# PMU.net
KiCad netlist of a schematic drawn in Altium Designer
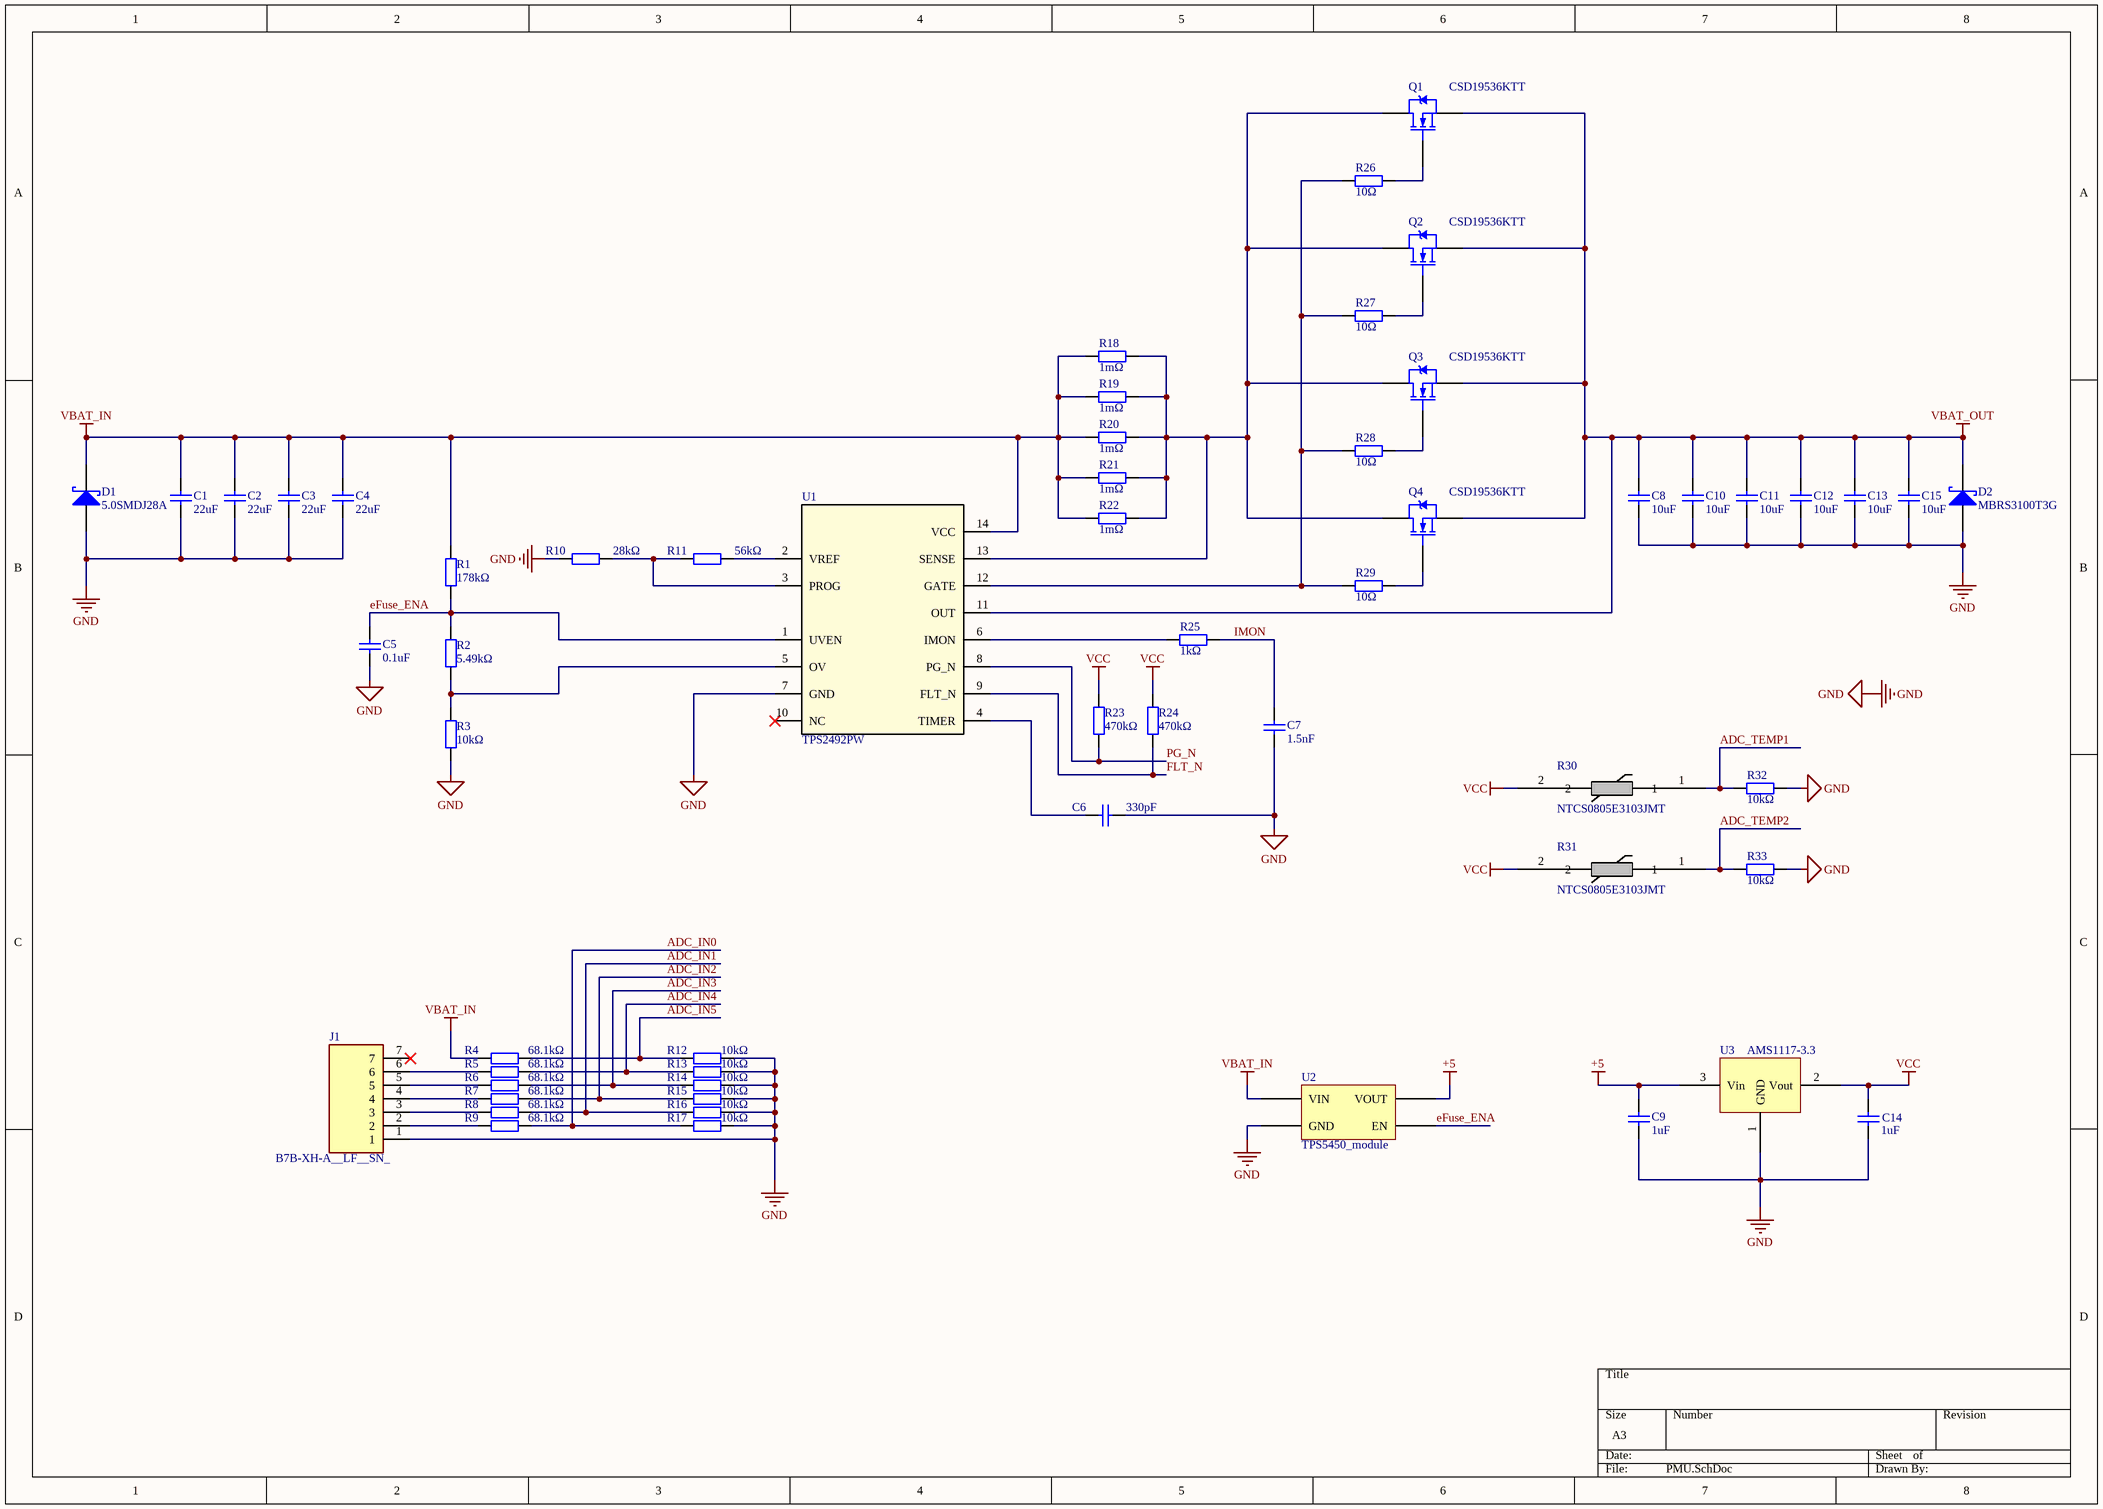
[diagram p0: PMU.SchDoc]

(export (version "E")
  (design (tool "Eeschema 10.0.6"))
  (components
    (comp (ref "C1")
      (value "22uF")
      (footprint "C1210")
      (description "VJ1210Y104MXCAT")
      (libsource (lib "NetTie") (part "Capacitor"))
    )
    (comp (ref "C2")
      (value "22uF")
      (footprint "C1210")
      (description "VJ1210Y104MXCAT")
      (libsource (lib "NetTie") (part "Capacitor"))
    )
    (comp (ref "C3")
      (value "22uF")
      (footprint "C1210")
      (description "VJ1210Y104MXCAT")
      (libsource (lib "NetTie") (part "Capacitor"))
    )
    (comp (ref "C4")
      (value "22uF")
      (footprint "C1210")
      (description "VJ1210Y104MXCAT")
      (libsource (lib "NetTie") (part "Capacitor"))
    )
    (comp (ref "C5") (value "0.1uF") (footprint "C0603") (libsource (lib "NetTie") (part "Capacitor")))
    (comp (ref "C6") (value "330pF") (footprint "C0603") (libsource (lib "NetTie") (part "Capacitor")))
    (comp (ref "C7") (value "1.5nF") (footprint "C0603") (libsource (lib "NetTie") (part "Capacitor")))
    (comp (ref "C8")
      (value "10uF")
      (footprint "C1210")
      (description "VJ1210Y104MXCAT")
      (libsource (lib "NetTie") (part "Capacitor"))
    )
    (comp (ref "C9")
      (value "1uF")
      (footprint "C0603")
      (description "VJ1210Y104MXCAT")
      (libsource (lib "NetTie") (part "Capacitor"))
    )
    (comp (ref "C10")
      (value "10uF")
      (footprint "C1210")
      (description "VJ1210Y104MXCAT")
      (libsource (lib "NetTie") (part "Capacitor"))
    )
    (comp (ref "C11")
      (value "10uF")
      (footprint "C1210")
      (description "VJ1210Y104MXCAT")
      (libsource (lib "NetTie") (part "Capacitor"))
    )
    (comp (ref "C12")
      (value "10uF")
      (footprint "C1210")
      (description "VJ1210Y104MXCAT")
      (libsource (lib "NetTie") (part "Capacitor"))
    )
    (comp (ref "C13")
      (value "10uF")
      (footprint "C1210")
      (description "VJ1210Y104MXCAT")
      (libsource (lib "NetTie") (part "Capacitor"))
    )
    (comp (ref "C14")
      (value "1uF")
      (footprint "C0603")
      (description "VJ1210Y104MXCAT")
      (libsource (lib "NetTie") (part "Capacitor"))
    )
    (comp (ref "C15")
      (value "10uF")
      (footprint "C1210")
      (description "VJ1210Y104MXCAT")
      (libsource (lib "NetTie") (part "Capacitor"))
    )
    (comp (ref "D1")
      (value "5.0SMDJ28A")
      (footprint "SMA(DO-214AC)")
      (libsource (lib "CommonUsedComponents") (part "Diode_Schottky"))
    )
    (comp (ref "D2")
      (value "MBRS3100T3G")
      (footprint "SMA(DO-214AC)")
      (description "Schottky Diodes & Rectifiers 3A 100V")
      (libsource (lib "CommonUsedComponents") (part "Diode_Schottky"))
    )
    (comp (ref "J1")
      (value "B7B-XH-A__LF__SN_")
      (footprint "SamacSys:SHDR7W64P0X250_1X7_1990X575X700P")
      (description "Connector")
      (fields (field (name "MANUFACTURER_PART_NUMBER") "B7B-XH-A (LF)(SN)"))
      (libsource (lib "Connectors") (part "B7B-XH-A__LF__SN_"))
    )
    (comp (ref "Q1")
      (value "CSD19536KTT")
      (footprint "KTT0002A")
      (description "100-V N-Channel NexFET™ Power MOSFET")
      (libsource (lib "NetTie") (part "NMOSFET"))
    )
    (comp (ref "Q2")
      (value "CSD19536KTT")
      (footprint "KTT0002A")
      (description "100-V N-Channel NexFET™ Power MOSFET")
      (libsource (lib "NetTie") (part "NMOSFET"))
    )
    (comp (ref "Q3")
      (value "CSD19536KTT")
      (footprint "KTT0002A")
      (description "100-V N-Channel NexFET™ Power MOSFET")
      (libsource (lib "NetTie") (part "NMOSFET"))
    )
    (comp (ref "Q4")
      (value "CSD19536KTT")
      (footprint "KTT0002A")
      (description "100-V N-Channel NexFET™ Power MOSFET")
      (libsource (lib "NetTie") (part "NMOSFET"))
    )
    (comp (ref "R1") (value "178kΩ") (footprint "R0603") (libsource (lib "NetTie") (part "Resistor")))
    (comp (ref "R2") (value "5.49kΩ") (footprint "R0603") (libsource (lib "NetTie") (part "Resistor")))
    (comp (ref "R3") (value "10kΩ") (footprint "R0603") (libsource (lib "NetTie") (part "Resistor")))
    (comp (ref "R4") (value "68.1kΩ") (footprint "R0603") (libsource (lib "") (part "Resistor_2")))
    (comp (ref "R5") (value "68.1kΩ") (footprint "R0603") (libsource (lib "") (part "Resistor_2")))
    (comp (ref "R6") (value "68.1kΩ") (footprint "R0603") (libsource (lib "") (part "Resistor_2")))
    (comp (ref "R7") (value "68.1kΩ") (footprint "R0603") (libsource (lib "") (part "Resistor_2")))
    (comp (ref "R8") (value "68.1kΩ") (footprint "R0603") (libsource (lib "") (part "Resistor_2")))
    (comp (ref "R9") (value "68.1kΩ") (footprint "R0603") (libsource (lib "") (part "Resistor_2")))
    (comp (ref "R10") (value "28kΩ") (footprint "R0603") (libsource (lib "") (part "Resistor_1")))
    (comp (ref "R11") (value "56kΩ") (footprint "R0603") (libsource (lib "") (part "Resistor_1")))
    (comp (ref "R12") (value "10kΩ") (footprint "R0603") (libsource (lib "") (part "Resistor_2")))
    (comp (ref "R13") (value "10kΩ") (footprint "R0603") (libsource (lib "") (part "Resistor_2")))
    (comp (ref "R14") (value "10kΩ") (footprint "R0603") (libsource (lib "") (part "Resistor_2")))
    (comp (ref "R15") (value "10kΩ") (footprint "R0603") (libsource (lib "") (part "Resistor_2")))
    (comp (ref "R16") (value "10kΩ") (footprint "R0603") (libsource (lib "") (part "Resistor_2")))
    (comp (ref "R17") (value "10kΩ") (footprint "R0603") (libsource (lib "") (part "Resistor_2")))
    (comp (ref "R18")
      (value "1mΩ")
      (footprint "2512_R")
      (description "CHSA2512R0010F")
      (libsource (lib "") (part "Resistor_1"))
    )
    (comp (ref "R19")
      (value "1mΩ")
      (footprint "2512_R")
      (description "CHSA2512R0010F")
      (libsource (lib "") (part "Resistor_1"))
    )
    (comp (ref "R20")
      (value "1mΩ")
      (footprint "2512_R")
      (description "CHSA2512R0010F")
      (libsource (lib "") (part "Resistor_1"))
    )
    (comp (ref "R21")
      (value "1mΩ")
      (footprint "2512_R")
      (description "CHSA2512R0010F")
      (libsource (lib "") (part "Resistor_1"))
    )
    (comp (ref "R22")
      (value "1mΩ")
      (footprint "2512_R")
      (description "CHSA2512R0010F")
      (libsource (lib "") (part "Resistor_1"))
    )
    (comp (ref "R23") (value "470kΩ") (footprint "R0603") (libsource (lib "") (part "Resistor_3")))
    (comp (ref "R24") (value "470kΩ") (footprint "R0603") (libsource (lib "") (part "Resistor_3")))
    (comp (ref "R25") (value "1kΩ") (footprint "R0603") (libsource (lib "") (part "Resistor_2")))
    (comp (ref "R26") (value "10Ω") (footprint "R0603") (libsource (lib "") (part "Resistor_2")))
    (comp (ref "R27") (value "10Ω") (footprint "R0603") (libsource (lib "") (part "Resistor_2")))
    (comp (ref "R28") (value "10Ω") (footprint "R0603") (libsource (lib "") (part "Resistor_2")))
    (comp (ref "R29") (value "10Ω") (footprint "R0603") (libsource (lib "") (part "Resistor_2")))
    (comp (ref "R30")
      (value "NTCS0805E3103JMT")
      (footprint "NTCS0805_VIS")
      (description "THERMISTOR NTC 10KOHM 3570K 0805")
      (fields (field (name "TOLERANCE") "5%"))
      (libsource (lib "Altium Content Vault") (part "NTCS0805E3103JMT"))
    )
    (comp (ref "R31")
      (value "NTCS0805E3103JMT")
      (footprint "NTCS0805_VIS")
      (description "THERMISTOR NTC 10KOHM 3570K 0805")
      (fields (field (name "TOLERANCE") "5%"))
      (libsource (lib "Altium Content Vault") (part "NTCS0805E3103JMT"))
    )
    (comp (ref "R32") (value "10kΩ") (footprint "R0603") (libsource (lib "") (part "Resistor_1")))
    (comp (ref "R33") (value "10kΩ") (footprint "R0603") (libsource (lib "") (part "Resistor_1")))
    (comp (ref "U1")
      (value "TPS2492PW")
      (footprint "PW0014A_N")
      (libsource (lib "PowerICs") (part "TPS2492PW"))
    )
    (comp (ref "U2")
      (value "TPS5450_module")
      (footprint "TPS5450_module")
      (libsource (lib "PowerICs") (part "TPS5450_module"))
    )
    (comp (ref "U3")
      (value "AMS1117-3.3")
      (footprint "SOT-223")
      (description "C347222")
      (libsource (lib "PowerICs") (part "AMS1117-3.3"))
    )
  )
  (nets
    (net (code "1") (name "+5") (class "Default")
      (node (ref "C9") (pin "2") (pinfunction "2_2") (pintype "passive"))
      (node (ref "U2") (pin "4") (pinfunction "VOUT_4") (pintype "passive"))
      (node (ref "U3") (pin "3") (pinfunction "Vin_3") (pintype "passive"))
    )
    (net (code "2") (name "/ADC_IN0") (class "Default")
      (node (ref "R17") (pin "2") (pinfunction "2_2") (pintype "passive"))
      (node (ref "R9") (pin "1") (pinfunction "1_1") (pintype "passive"))
    )
    (net (code "3") (name "/ADC_IN1") (class "Default")
      (node (ref "R16") (pin "2") (pinfunction "2_2") (pintype "passive"))
      (node (ref "R8") (pin "1") (pinfunction "1_1") (pintype "passive"))
    )
    (net (code "4") (name "/ADC_IN2") (class "Default")
      (node (ref "R15") (pin "2") (pinfunction "2_2") (pintype "passive"))
      (node (ref "R7") (pin "1") (pinfunction "1_1") (pintype "passive"))
    )
    (net (code "5") (name "/ADC_IN3") (class "Default")
      (node (ref "R14") (pin "2") (pinfunction "2_2") (pintype "passive"))
      (node (ref "R6") (pin "1") (pinfunction "1_1") (pintype "passive"))
    )
    (net (code "6") (name "/ADC_IN4") (class "Default")
      (node (ref "R13") (pin "2") (pinfunction "2_2") (pintype "passive"))
      (node (ref "R5") (pin "1") (pinfunction "1_1") (pintype "passive"))
    )
    (net (code "7") (name "/ADC_IN5") (class "Default")
      (node (ref "R12") (pin "2") (pinfunction "2_2") (pintype "passive"))
      (node (ref "R4") (pin "1") (pinfunction "1_1") (pintype "passive"))
    )
    (net (code "8") (name "/ADC_TEMP1") (class "Default")
      (node (ref "R30") (pin "1") (pinfunction "1_1") (pintype "passive"))
      (node (ref "R32") (pin "1") (pinfunction "1_1") (pintype "passive"))
    )
    (net (code "9") (name "/ADC_TEMP2") (class "Default")
      (node (ref "R31") (pin "1") (pinfunction "1_1") (pintype "passive"))
      (node (ref "R33") (pin "1") (pinfunction "1_1") (pintype "passive"))
    )
    (net (code "10") (name "/FLT_N") (class "Default")
      (node (ref "R24") (pin "2") (pinfunction "2_2") (pintype "passive"))
      (node (ref "U1") (pin "9") (pinfunction "FLT_N_9") (pintype "passive"))
    )
    (net (code "11") (name "/IMON") (class "Default")
      (node (ref "C7") (pin "2") (pinfunction "2_2") (pintype "passive"))
      (node (ref "R25") (pin "1") (pinfunction "1_1") (pintype "passive"))
    )
    (net (code "12") (name "/PG_N") (class "Default")
      (node (ref "R23") (pin "2") (pinfunction "2_2") (pintype "passive"))
      (node (ref "U1") (pin "8") (pinfunction "PG_N_8") (pintype "passive"))
    )
    (net (code "13") (name "/eFuse_ENA") (class "Default")
      (node (ref "C5") (pin "2") (pinfunction "2_2") (pintype "passive"))
      (node (ref "R1") (pin "1") (pinfunction "1_1") (pintype "passive"))
      (node (ref "R2") (pin "2") (pinfunction "2_2") (pintype "passive"))
      (node (ref "U1") (pin "1") (pinfunction "UVEN_1") (pintype "passive"))
      (node (ref "U2") (pin "3") (pinfunction "EN_3") (pintype "passive"))
    )
    (net (code "14") (name "GND") (class "Default")
      (node (ref "C1") (pin "1") (pinfunction "1_1") (pintype "passive"))
      (node (ref "C10") (pin "1") (pinfunction "1_1") (pintype "passive"))
      (node (ref "C11") (pin "1") (pinfunction "1_1") (pintype "passive"))
      (node (ref "C12") (pin "1") (pinfunction "1_1") (pintype "passive"))
      (node (ref "C13") (pin "1") (pinfunction "1_1") (pintype "passive"))
      (node (ref "C14") (pin "1") (pinfunction "1_1") (pintype "passive"))
      (node (ref "C15") (pin "1") (pinfunction "1_1") (pintype "passive"))
      (node (ref "C2") (pin "1") (pinfunction "1_1") (pintype "passive"))
      (node (ref "C3") (pin "1") (pinfunction "1_1") (pintype "passive"))
      (node (ref "C4") (pin "1") (pinfunction "1_1") (pintype "passive"))
      (node (ref "C5") (pin "1") (pinfunction "1_1") (pintype "passive"))
      (node (ref "C6") (pin "1") (pinfunction "1_1") (pintype "passive"))
      (node (ref "C7") (pin "1") (pinfunction "1_1") (pintype "passive"))
      (node (ref "C8") (pin "1") (pinfunction "1_1") (pintype "passive"))
      (node (ref "C9") (pin "1") (pinfunction "1_1") (pintype "passive"))
      (node (ref "D1") (pin "1") (pinfunction "A_1") (pintype "passive"))
      (node (ref "D2") (pin "1") (pinfunction "A_1") (pintype "passive"))
      (node (ref "J1") (pin "1") (pinfunction "1_1") (pintype "passive"))
      (node (ref "R10") (pin "1") (pinfunction "1_1") (pintype "passive"))
      (node (ref "R12") (pin "1") (pinfunction "1_1") (pintype "passive"))
      (node (ref "R13") (pin "1") (pinfunction "1_1") (pintype "passive"))
      (node (ref "R14") (pin "1") (pinfunction "1_1") (pintype "passive"))
      (node (ref "R15") (pin "1") (pinfunction "1_1") (pintype "passive"))
      (node (ref "R16") (pin "1") (pinfunction "1_1") (pintype "passive"))
      (node (ref "R17") (pin "1") (pinfunction "1_1") (pintype "passive"))
      (node (ref "R3") (pin "1") (pinfunction "1_1") (pintype "passive"))
      (node (ref "R32") (pin "2") (pinfunction "2_2") (pintype "passive"))
      (node (ref "R33") (pin "2") (pinfunction "2_2") (pintype "passive"))
      (node (ref "U1") (pin "7") (pinfunction "GND_7") (pintype "power_in"))
      (node (ref "U2") (pin "2") (pinfunction "GND_2") (pintype "passive"))
      (node (ref "U3") (pin "1") (pinfunction "GND_1") (pintype "passive"))
    )
    (net (code "15") (name "Net-(J1-Pad2)") (class "Default")
      (node (ref "J1") (pin "2") (pinfunction "2_2") (pintype "passive"))
      (node (ref "R9") (pin "2") (pinfunction "2_2") (pintype "passive"))
    )
    (net (code "16") (name "Net-(J1-Pad3)") (class "Default")
      (node (ref "J1") (pin "3") (pinfunction "3_3") (pintype "passive"))
      (node (ref "R8") (pin "2") (pinfunction "2_2") (pintype "passive"))
    )
    (net (code "17") (name "Net-(J1-Pad4)") (class "Default")
      (node (ref "J1") (pin "4") (pinfunction "4_4") (pintype "passive"))
      (node (ref "R7") (pin "2") (pinfunction "2_2") (pintype "passive"))
    )
    (net (code "18") (name "Net-(J1-Pad5)") (class "Default")
      (node (ref "J1") (pin "5") (pinfunction "5_5") (pintype "passive"))
      (node (ref "R6") (pin "2") (pinfunction "2_2") (pintype "passive"))
    )
    (net (code "19") (name "Net-(J1-Pad6)") (class "Default")
      (node (ref "J1") (pin "6") (pinfunction "6_6") (pintype "passive"))
      (node (ref "R5") (pin "2") (pinfunction "2_2") (pintype "passive"))
    )
    (net (code "20") (name "Net-(Q1-D)") (class "Default")
      (node (ref "Q1") (pin "2") (pinfunction "D_2") (pintype "passive"))
      (node (ref "Q2") (pin "2") (pinfunction "D_2") (pintype "passive"))
      (node (ref "Q3") (pin "2") (pinfunction "D_2") (pintype "passive"))
      (node (ref "Q4") (pin "2") (pinfunction "D_2") (pintype "passive"))
      (node (ref "R18") (pin "2") (pinfunction "2_2") (pintype "passive"))
      (node (ref "R19") (pin "2") (pinfunction "2_2") (pintype "passive"))
      (node (ref "R20") (pin "2") (pinfunction "2_2") (pintype "passive"))
      (node (ref "R21") (pin "2") (pinfunction "2_2") (pintype "passive"))
      (node (ref "R22") (pin "2") (pinfunction "2_2") (pintype "passive"))
      (node (ref "U1") (pin "13") (pinfunction "SENSE_13") (pintype "passive"))
    )
    (net (code "21") (name "Net-(Q1-G)") (class "Default")
      (node (ref "Q1") (pin "1") (pinfunction "G_1") (pintype "passive"))
      (node (ref "R26") (pin "1") (pinfunction "1_1") (pintype "passive"))
    )
    (net (code "22") (name "Net-(Q2-G)") (class "Default")
      (node (ref "Q2") (pin "1") (pinfunction "G_1") (pintype "passive"))
      (node (ref "R27") (pin "1") (pinfunction "1_1") (pintype "passive"))
    )
    (net (code "23") (name "Net-(Q3-G)") (class "Default")
      (node (ref "Q3") (pin "1") (pinfunction "G_1") (pintype "passive"))
      (node (ref "R28") (pin "1") (pinfunction "1_1") (pintype "passive"))
    )
    (net (code "24") (name "Net-(Q4-G)") (class "Default")
      (node (ref "Q4") (pin "1") (pinfunction "G_1") (pintype "passive"))
      (node (ref "R29") (pin "1") (pinfunction "1_1") (pintype "passive"))
    )
    (net (code "25") (name "Net-(U1-GATE)") (class "Default")
      (node (ref "R26") (pin "2") (pinfunction "2_2") (pintype "passive"))
      (node (ref "R27") (pin "2") (pinfunction "2_2") (pintype "passive"))
      (node (ref "R28") (pin "2") (pinfunction "2_2") (pintype "passive"))
      (node (ref "R29") (pin "2") (pinfunction "2_2") (pintype "passive"))
      (node (ref "U1") (pin "12") (pinfunction "GATE_12") (pintype "passive"))
    )
    (net (code "26") (name "Net-(U1-IMON)") (class "Default")
      (node (ref "R25") (pin "2") (pinfunction "2_2") (pintype "passive"))
      (node (ref "U1") (pin "6") (pinfunction "IMON_6") (pintype "passive"))
    )
    (net (code "27") (name "Net-(U1-OV)") (class "Default")
      (node (ref "R2") (pin "1") (pinfunction "1_1") (pintype "passive"))
      (node (ref "R3") (pin "2") (pinfunction "2_2") (pintype "passive"))
      (node (ref "U1") (pin "5") (pinfunction "OV_5") (pintype "passive"))
    )
    (net (code "28") (name "Net-(U1-PROG)") (class "Default")
      (node (ref "R10") (pin "2") (pinfunction "2_2") (pintype "passive"))
      (node (ref "R11") (pin "1") (pinfunction "1_1") (pintype "passive"))
      (node (ref "U1") (pin "3") (pinfunction "PROG_3") (pintype "passive"))
    )
    (net (code "29") (name "Net-(U1-TIMER)") (class "Default")
      (node (ref "C6") (pin "2") (pinfunction "2_2") (pintype "passive"))
      (node (ref "U1") (pin "4") (pinfunction "TIMER_4") (pintype "passive"))
    )
    (net (code "30") (name "Net-(U1-VREF)") (class "Default")
      (node (ref "R11") (pin "2") (pinfunction "2_2") (pintype "passive"))
      (node (ref "U1") (pin "2") (pinfunction "VREF_2") (pintype "passive"))
    )
    (net (code "31") (name "VBAT_IN") (class "Default")
      (node (ref "C1") (pin "2") (pinfunction "2_2") (pintype "passive"))
      (node (ref "C2") (pin "2") (pinfunction "2_2") (pintype "passive"))
      (node (ref "C3") (pin "2") (pinfunction "2_2") (pintype "passive"))
      (node (ref "C4") (pin "2") (pinfunction "2_2") (pintype "passive"))
      (node (ref "D1") (pin "2") (pinfunction "K_2") (pintype "passive"))
      (node (ref "R1") (pin "2") (pinfunction "2_2") (pintype "passive"))
      (node (ref "R18") (pin "1") (pinfunction "1_1") (pintype "passive"))
      (node (ref "R19") (pin "1") (pinfunction "1_1") (pintype "passive"))
      (node (ref "R20") (pin "1") (pinfunction "1_1") (pintype "passive"))
      (node (ref "R21") (pin "1") (pinfunction "1_1") (pintype "passive"))
      (node (ref "R22") (pin "1") (pinfunction "1_1") (pintype "passive"))
      (node (ref "R4") (pin "2") (pinfunction "2_2") (pintype "passive"))
      (node (ref "U1") (pin "14") (pinfunction "VCC_14") (pintype "power_in"))
      (node (ref "U2") (pin "1") (pinfunction "VIN_1") (pintype "passive"))
    )
    (net (code "32") (name "VBAT_OUT") (class "Default")
      (node (ref "C10") (pin "2") (pinfunction "2_2") (pintype "passive"))
      (node (ref "C11") (pin "2") (pinfunction "2_2") (pintype "passive"))
      (node (ref "C12") (pin "2") (pinfunction "2_2") (pintype "passive"))
      (node (ref "C13") (pin "2") (pinfunction "2_2") (pintype "passive"))
      (node (ref "C15") (pin "2") (pinfunction "2_2") (pintype "passive"))
      (node (ref "C8") (pin "2") (pinfunction "2_2") (pintype "passive"))
      (node (ref "D2") (pin "2") (pinfunction "K_2") (pintype "passive"))
      (node (ref "Q1") (pin "3") (pinfunction "S_3") (pintype "passive"))
      (node (ref "Q2") (pin "3") (pinfunction "S_3") (pintype "passive"))
      (node (ref "Q3") (pin "3") (pinfunction "S_3") (pintype "passive"))
      (node (ref "Q4") (pin "3") (pinfunction "S_3") (pintype "passive"))
      (node (ref "U1") (pin "11") (pinfunction "OUT_11") (pintype "passive"))
    )
    (net (code "33") (name "VCC") (class "Default")
      (node (ref "C14") (pin "2") (pinfunction "2_2") (pintype "passive"))
      (node (ref "R23") (pin "1") (pinfunction "1_1") (pintype "passive"))
      (node (ref "R24") (pin "1") (pinfunction "1_1") (pintype "passive"))
      (node (ref "R30") (pin "2") (pinfunction "2_2") (pintype "passive"))
      (node (ref "R31") (pin "2") (pinfunction "2_2") (pintype "passive"))
      (node (ref "U3") (pin "2") (pinfunction "Vout_2") (pintype "passive"))
    )
    (net (code "34") (name "unconnected-(J1-Pad7)") (class "Default")
      (node (ref "J1") (pin "7") (pinfunction "7_7") (pintype "passive+no_connect"))
    )
    (net (code "35") (name "unconnected-(U1-NC-Pad10)") (class "Default")
      (node (ref "U1") (pin "10") (pinfunction "NC_10") (pintype "passive+no_connect"))
    )
  )
)
